# Control.net
KiCad netlist of a schematic drawn in Altium Designer
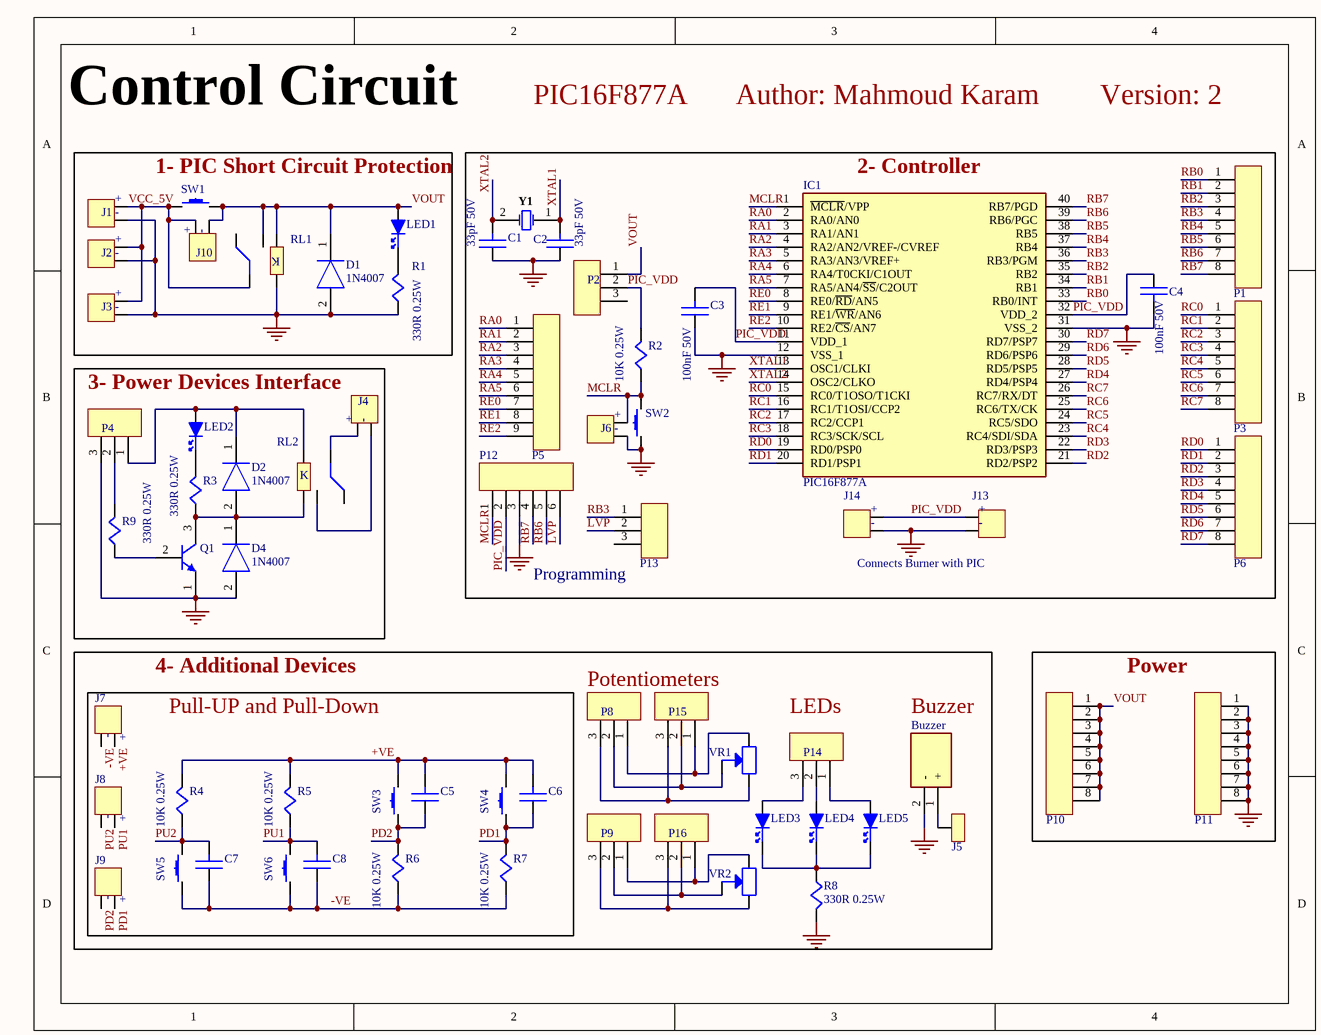
[diagram p0: Control.SchDoc]

(export (version "E")
  (design (tool "Eeschema 10.0.6"))
  (components
    (comp (ref "Buzzer")
      (value "Buzzer 5V")
      (footprint "MyLib:Buzzer 7.62mm pitch 12mm dia")
      (description "Loudspeaker or Buzzer")
      (fields (field (name "MANUFACTURER_PART_NUMBER") "7243178"))
      (libsource (lib "MyLib") (part "Speaker"))
    )
    (comp (ref "C1")
      (value "33pF 50V")
      (footprint "Cap Ceramic 104")
      (description "Capacitor Ceramic")
      (fields
        (field (name "MANUFACTURER") "KEMET")
        (field (name "MANUFACTURER PART NUMBER") "C320C104M5R5TA7301")
      )
      (libsource (lib "MyLib") (part "Ceramic_Capacitors"))
    )
    (comp (ref "C2")
      (value "33pF 50V")
      (footprint "Cap Ceramic 104")
      (description "Capacitor Ceramic")
      (fields
        (field (name "MANUFACTURER") "KEMET")
        (field (name "MANUFACTURER PART NUMBER") "C320C104M5R5TA7301")
      )
      (libsource (lib "MyLib") (part "Ceramic_Capacitors"))
    )
    (comp (ref "C3")
      (value "100nF 50V")
      (footprint "Cap Ceramic 104 2.54")
      (description "Capacitor Ceramic")
      (fields
        (field (name "MANUFACTURER") "KEMET")
        (field (name "MANUFACTURER PART NUMBER") "C320C104M5R5TA7301")
      )
      (libsource (lib "MyLib") (part "Ceramic_Capacitors"))
    )
    (comp (ref "C4")
      (value "100nF 50V")
      (footprint "Cap Ceramic 104 2.54")
      (description "Capacitor Ceramic")
      (fields
        (field (name "MANUFACTURER") "KEMET")
        (field (name "MANUFACTURER PART NUMBER") "C320C104M5R5TA7301")
      )
      (libsource (lib "MyLib") (part "Ceramic_Capacitors"))
    )
    (comp (ref "C5")
      (value "100nF 50V")
      (footprint "Cap Ceramic 104")
      (description "Capacitor Ceramic")
      (fields
        (field (name "MANUFACTURER") "KEMET")
        (field (name "MANUFACTURER PART NUMBER") "C320C104M5R5TA7301")
      )
      (libsource (lib "MyLib") (part "Ceramic_Capacitors"))
    )
    (comp (ref "C6")
      (value "100nF 50V")
      (footprint "Cap Ceramic 104")
      (description "Capacitor Ceramic")
      (fields
        (field (name "MANUFACTURER") "KEMET")
        (field (name "MANUFACTURER PART NUMBER") "C320C104M5R5TA7301")
      )
      (libsource (lib "MyLib") (part "Ceramic_Capacitors"))
    )
    (comp (ref "C7")
      (value "100nF 50V")
      (footprint "Cap Ceramic 104")
      (description "Capacitor Ceramic")
      (fields
        (field (name "MANUFACTURER") "KEMET")
        (field (name "MANUFACTURER PART NUMBER") "C320C104M5R5TA7301")
      )
      (libsource (lib "MyLib") (part "Ceramic_Capacitors"))
    )
    (comp (ref "C8")
      (value "100nF 50V")
      (footprint "Cap Ceramic 104")
      (description "Capacitor Ceramic")
      (fields
        (field (name "MANUFACTURER") "KEMET")
        (field (name "MANUFACTURER PART NUMBER") "C320C104M5R5TA7301")
      )
      (libsource (lib "MyLib") (part "Ceramic_Capacitors"))
    )
    (comp (ref "D1")
      (value "1N4007")
      (footprint "Diode 10.16mm TH H")
      (description "Diodes")
      (fields
        (field (name "MANUFACTURER_PART_NUMBER") "1N4007-E3/53")
        (field (name "MOUSER PART NUMBER") "625-1N4007-E3/53")
      )
      (libsource (lib "MyLib") (part "Diodes"))
    )
    (comp (ref "D2")
      (value "1N4007")
      (footprint "Diode 2.54mm TH V")
      (description "Diodes")
      (fields
        (field (name "MANUFACTURER_PART_NUMBER") "1N4007-E3/53")
        (field (name "MOUSER PART NUMBER") "625-1N4007-E3/53")
      )
      (libsource (lib "MyLib") (part "Diodes"))
    )
    (comp (ref "D4")
      (value "1N4007")
      (footprint "Diode 2.54mm TH V")
      (description "Diodes")
      (fields
        (field (name "MANUFACTURER_PART_NUMBER") "1N4007-E3/53")
        (field (name "MOUSER PART NUMBER") "625-1N4007-E3/53")
      )
      (libsource (lib "MyLib") (part "Diodes"))
    )
    (comp (ref "IC1")
      (value "PIC16F877A")
      (footprint "PIC16F877A TH With Socket")
      (description "Integrated Circuit")
      (fields
        (field (name "MANUFACTURER_PART_NUMBER") "PIC16F877A-I/P")
        (field (name "MOUSER PART NUMBER") "579-PIC16F877A-I/P")
      )
      (libsource (lib "MyLib") (part "PIC16F877A"))
    )
    (comp (ref "J1")
      (value "JST on PCB Connector 2 pins")
      (footprint "JST_B2B TH")
      (description "Terminals 2POS")
      (fields
        (field (name "MANUFACTURER") "Phoenix Contact")
        (field (name "MANUFACTURER PART NUMBER") "1729128")
      )
      (libsource (lib "") (part "Terminal_Block_2Pos_1"))
    )
    (comp (ref "J2")
      (value "Terminal Block Green 5.08mm")
      (footprint "Screw Terminal Block 5.08mm TH Green")
      (description "Terminals 2POS")
      (fields
        (field (name "MANUFACTURER") "Phoenix Contact")
        (field (name "MANUFACTURER PART NUMBER") "1729128")
      )
      (libsource (lib "") (part "Terminal_Block_2Pos_1"))
    )
    (comp (ref "J3")
      (value "DC Power Jack PJ002")
      (footprint "DC Power Jack 2.1mm PJ-002AH TH")
      (description "Terminals 2POS")
      (fields
        (field (name "MANUFACTURER") "Phoenix Contact")
        (field (name "MANUFACTURER PART NUMBER") "1729128")
      )
      (libsource (lib "") (part "Terminal_Block_2Pos_1"))
    )
    (comp (ref "J4")
      (value "Terminal Block Blue 5.08mm")
      (footprint "Screw Terminal Block 5.08mm TH Blue")
      (description "Terminals 2POS")
      (fields
        (field (name "MANUFACTURER") "Phoenix Contact")
        (field (name "MANUFACTURER PART NUMBER") "1729128")
      )
      (libsource (lib "") (part "Terminal_Block_2Pos_2"))
    )
    (comp (ref "J5") (value "Pin") (footprint "Pin") (libsource (lib "MyLib") (part "Pin")))
    (comp (ref "J6")
      (value "Header male 2 ways")
      (footprint "Header Male 2.54mm 2 Pins TH")
      (description "Terminals 2POS")
      (fields
        (field (name "MANUFACTURER") "Phoenix Contact")
        (field (name "MANUFACTURER PART NUMBER") "1729128")
      )
      (libsource (lib "") (part "Terminal_Block_2Pos_1"))
    )
    (comp (ref "J7")
      (value "Header male 2 ways")
      (footprint "Header Male 2.54mm 2 Pins TH")
      (description "Terminals 2POS")
      (fields
        (field (name "MANUFACTURER") "Phoenix Contact")
        (field (name "MANUFACTURER PART NUMBER") "1729128")
      )
      (libsource (lib "MyLib") (part "Terminal_Block_2Pos"))
    )
    (comp (ref "J8")
      (value "Header male 2 ways")
      (footprint "Header Male 2.54mm 2 Pins TH")
      (description "Terminals 2POS")
      (fields
        (field (name "MANUFACTURER") "Phoenix Contact")
        (field (name "MANUFACTURER PART NUMBER") "1729128")
      )
      (libsource (lib "MyLib") (part "Terminal_Block_2Pos"))
    )
    (comp (ref "J9")
      (value "Header male 2 ways")
      (footprint "Header Male 2.54mm 2 Pins TH")
      (description "Terminals 2POS")
      (fields
        (field (name "MANUFACTURER") "Phoenix Contact")
        (field (name "MANUFACTURER PART NUMBER") "1729128")
      )
      (libsource (lib "MyLib") (part "Terminal_Block_2Pos"))
    )
    (comp (ref "J10")
      (value "Header male 2 ways")
      (footprint "Header Male 2.54mm 2 Pins TH")
      (description "Terminals 2POS")
      (fields
        (field (name "MANUFACTURER") "Phoenix Contact")
        (field (name "MANUFACTURER PART NUMBER") "1729128")
      )
      (libsource (lib "") (part "Terminal_Block_2Pos_3"))
    )
    (comp (ref "J13")
      (value "Header male 2 ways")
      (footprint "Header Male 2.54mm 2 Pins TH")
      (description "Terminals 2POS")
      (fields
        (field (name "MANUFACTURER") "Phoenix Contact")
        (field (name "MANUFACTURER PART NUMBER") "1729128")
      )
      (libsource (lib "MyLib") (part "Terminal_Block_2Pos"))
    )
    (comp (ref "J14")
      (value "Header male 2 ways")
      (footprint "Header Male 2.54mm 2 Pins TH")
      (description "Terminals 2POS")
      (fields
        (field (name "MANUFACTURER") "Phoenix Contact")
        (field (name "MANUFACTURER PART NUMBER") "1729128")
      )
      (libsource (lib "") (part "Terminal_Block_2Pos_1"))
    )
    (comp (ref "LED1")
      (value "RED 5mm")
      (footprint "LED 5mm Red TH")
      (description "LEDs")
      (fields
        (field (name "MANUFACTURER") "Vishay Semiconductors")
        (field (name "MANUFACTURER PART NUMBER") "TLDR5400")
      )
      (libsource (lib "MyLib") (part "LEDs_Single"))
    )
    (comp (ref "LED2")
      (value "Green 5mm")
      (footprint "LED 5mm Green TH")
      (description "LEDs")
      (fields
        (field (name "MANUFACTURER") "Vishay Semiconductors")
        (field (name "MANUFACTURER PART NUMBER") "TLDR5400")
      )
      (libsource (lib "MyLib") (part "LEDs_Single"))
    )
    (comp (ref "LED3")
      (value "RED 5mm")
      (footprint "LED 5mm Red TH")
      (description "LEDs")
      (fields
        (field (name "MANUFACTURER") "Vishay Semiconductors")
        (field (name "MANUFACTURER PART NUMBER") "TLDR5400")
      )
      (libsource (lib "MyLib") (part "LEDs_Single"))
    )
    (comp (ref "LED4")
      (value "Green 5mm")
      (footprint "LED 5mm Green TH")
      (description "LEDs")
      (fields
        (field (name "MANUFACTURER") "Vishay Semiconductors")
        (field (name "MANUFACTURER PART NUMBER") "TLDR5400")
      )
      (libsource (lib "MyLib") (part "LEDs_Single"))
    )
    (comp (ref "LED5")
      (value "Yellow 5mm")
      (footprint "LED 5mm Yellow TH")
      (description "LEDs")
      (fields
        (field (name "MANUFACTURER") "Vishay Semiconductors")
        (field (name "MANUFACTURER PART NUMBER") "TLDR5400")
      )
      (libsource (lib "MyLib") (part "LEDs_Single"))
    )
    (comp (ref "P1")
      (value "Header male 8 ways")
      (footprint "Header Male 2.54mm 8 Pins TH")
      (fields (field (name "MANUFACTURER") "3M"))
      (libsource (lib "") (part "Terminal_Block_8Pos_1"))
    )
    (comp (ref "P2")
      (value "Header male 3 ways with jumper")
      (footprint "Header Male 2.54mm 3 Pins with jumper TH")
      (fields (field (name "MANUFACTURER") "3M"))
      (libsource (lib "") (part "Terminal_Block_3Pos_1"))
    )
    (comp (ref "P3")
      (value "Header male 8 ways")
      (footprint "Header Male 2.54mm 8 Pins TH")
      (fields (field (name "MANUFACTURER") "3M"))
      (libsource (lib "") (part "Terminal_Block_8Pos_1"))
    )
    (comp (ref "P4")
      (value "Header male 3 ways")
      (footprint "Header Male 2.54mm 3 Pins TH")
      (fields (field (name "MANUFACTURER") "3M"))
      (libsource (lib "MyLib") (part "Terminal_Block_3Pos"))
    )
    (comp (ref "P5")
      (value "Header male 9 ways")
      (footprint "Header Male 2.54mm 9 Pins TH")
      (fields (field (name "MANUFACTURER") "3M"))
      (libsource (lib "MyLib") (part "Terminal_Block_9Pos"))
    )
    (comp (ref "P6")
      (value "Header male 8 ways")
      (footprint "Header Male 2.54mm 8 Pins TH")
      (fields (field (name "MANUFACTURER") "3M"))
      (libsource (lib "") (part "Terminal_Block_8Pos_1"))
    )
    (comp (ref "P8")
      (value "Header male 3 ways")
      (footprint "Header Male 2.54mm 3 Pins TH")
      (fields (field (name "MANUFACTURER") "3M"))
      (libsource (lib "MyLib") (part "Terminal_Block_3Pos"))
    )
    (comp (ref "P9")
      (value "Header male 3 ways")
      (footprint "Header Male 2.54mm 3 Pins TH")
      (fields (field (name "MANUFACTURER") "3M"))
      (libsource (lib "MyLib") (part "Terminal_Block_3Pos"))
    )
    (comp (ref "P10")
      (value "Header male 8 ways")
      (footprint "Header Male 2.54mm 8 Pins TH")
      (fields (field (name "MANUFACTURER") "3M"))
      (libsource (lib "MyLib") (part "Terminal_Block_8Pos"))
    )
    (comp (ref "P11")
      (value "Header male 8 ways")
      (footprint "Header Male 2.54mm 8 Pins TH")
      (fields (field (name "MANUFACTURER") "3M"))
      (libsource (lib "MyLib") (part "Terminal_Block_8Pos"))
    )
    (comp (ref "P12")
      (value "Header male 6 ways")
      (footprint "Header Male 2.54mm 6 Pins TH")
      (fields (field (name "MANUFACTURER") "3M"))
      (libsource (lib "MyLib") (part "Terminal_Block_6Pos"))
    )
    (comp (ref "P13")
      (value "Header male 3 ways with jumper")
      (footprint "Header Male 2.54mm 3 Pins with jumper TH")
      (fields (field (name "MANUFACTURER") "3M"))
      (libsource (lib "MyLib") (part "Terminal_Block_3Pos"))
    )
    (comp (ref "P14")
      (value "Header male 3 ways")
      (footprint "Header Male 2.54mm 3 Pins TH")
      (fields (field (name "MANUFACTURER") "3M"))
      (libsource (lib "MyLib") (part "Terminal_Block_3Pos"))
    )
    (comp (ref "P15")
      (value "Header male 3 ways")
      (footprint "Header Male 2.54mm 3 Pins TH")
      (fields (field (name "MANUFACTURER") "3M"))
      (libsource (lib "MyLib") (part "Terminal_Block_3Pos"))
    )
    (comp (ref "P16")
      (value "Header male 3 ways")
      (footprint "Header Male 2.54mm 3 Pins TH")
      (fields (field (name "MANUFACTURER") "3M"))
      (libsource (lib "MyLib") (part "Terminal_Block_3Pos"))
    )
    (comp (ref "Q1")
      (value "Transistor PN2222")
      (footprint "PN2222")
      (description "NPN General-Purpose Amplifier, 40 V, -55 to 150 degC, 3-Pin TO-92, RoHS, Bulk")
      (fields (field (name "MANUFACTURER") "Fairchild") (field (name "POWER") "625mW"))
      (libsource (lib "Mahmoud Karam") (part "BJT-NPN-EBC-3"))
    )
    (comp (ref "R1")
      (value "330R 0.25W")
      (footprint "Res 7.62mm H TH")
      (description "Resistors")
      (fields
        (field (name "MANUFACTURER") "Yageo")
        (field (name "MANUFACTURER PART NUMBER") "CFR-25JB-52-100K")
      )
      (libsource (lib "MyLib") (part "Resistors_Single"))
    )
    (comp (ref "R2")
      (value "10K 0.25W")
      (footprint "Res 7.62mm H TH")
      (description "Resistors")
      (fields
        (field (name "MANUFACTURER") "Yageo")
        (field (name "MANUFACTURER PART NUMBER") "CFR-25JB-52-100K")
      )
      (libsource (lib "MyLib") (part "Resistors_Single"))
    )
    (comp (ref "R3")
      (value "330R 0.25W")
      (footprint "Res 2.54mm V TH")
      (description "Resistors")
      (fields
        (field (name "MANUFACTURER") "Yageo")
        (field (name "MANUFACTURER PART NUMBER") "CFR-25JB-52-100K")
      )
      (libsource (lib "MyLib") (part "Resistors_Single"))
    )
    (comp (ref "R4")
      (value "10K 0.25W")
      (footprint "Res 2.54mm V TH")
      (description "Resistors")
      (fields
        (field (name "MANUFACTURER") "Yageo")
        (field (name "MANUFACTURER PART NUMBER") "CFR-25JB-52-100K")
      )
      (libsource (lib "MyLib") (part "Resistors_Single"))
    )
    (comp (ref "R5")
      (value "10K 0.25W")
      (footprint "Res 2.54mm V TH")
      (description "Resistors")
      (fields
        (field (name "MANUFACTURER") "Yageo")
        (field (name "MANUFACTURER PART NUMBER") "CFR-25JB-52-100K")
      )
      (libsource (lib "MyLib") (part "Resistors_Single"))
    )
    (comp (ref "R6")
      (value "10K 0.25W")
      (footprint "Res 2.54mm V TH")
      (description "Resistors")
      (fields
        (field (name "MANUFACTURER") "Yageo")
        (field (name "MANUFACTURER PART NUMBER") "CFR-25JB-52-100K")
      )
      (libsource (lib "MyLib") (part "Resistors_Single"))
    )
    (comp (ref "R7")
      (value "10K 0.25W")
      (footprint "Res 2.54mm V TH")
      (description "Resistors")
      (fields
        (field (name "MANUFACTURER") "Yageo")
        (field (name "MANUFACTURER PART NUMBER") "CFR-25JB-52-100K")
      )
      (libsource (lib "MyLib") (part "Resistors_Single"))
    )
    (comp (ref "R8")
      (value "330R 0.25W")
      (footprint "Res 7.62mm H TH")
      (description "Resistors")
      (fields
        (field (name "MANUFACTURER") "Yageo")
        (field (name "MANUFACTURER PART NUMBER") "CFR-25JB-52-100K")
      )
      (libsource (lib "MyLib") (part "Resistors_Single"))
    )
    (comp (ref "R9")
      (value "330R 0.25W")
      (footprint "Res 2.54mm V TH")
      (description "Resistors")
      (fields
        (field (name "MANUFACTURER") "Yageo")
        (field (name "MANUFACTURER PART NUMBER") "CFR-25JB-52-100K")
      )
      (libsource (lib "MyLib") (part "Resistors_Single"))
    )
    (comp (ref "RL1")
      (value "Relay 5V SRD-05VDC-SL-C")
      (footprint "Relay SRD-05VDC-SL-C")
      (description "Relay SPDT")
      (fields
        (field (name "MANUFACTURER") "TE Connectivity P&B")
        (field (name "MANUFACTURER PART NUMBER") "1-1721150-0")
      )
      (libsource (lib "") (part "Relay_SPDT_1"))
    )
    (comp (ref "RL2")
      (value "Relay 5V SRD-05VDC-SL-C")
      (footprint "Relay SRD-05VDC-SL-C")
      (description "Relay SPDT")
      (fields
        (field (name "MANUFACTURER") "TE Connectivity P&B")
        (field (name "MANUFACTURER PART NUMBER") "1-1721150-0")
      )
      (libsource (lib "MyLib") (part "Relay_SPDT"))
    )
    (comp (ref "SW1")
      (value "Tactile Switch 4 poles")
      (footprint "Tactile switch 6*6*5 TH")
      (description "Switches")
      (fields
        (field (name "MANUFACTURER") "E-Switch")
        (field (name "MANUFACTURER PART NUMBER") "TL1105LF160Q")
      )
      (libsource (lib "MyLib") (part "Switches_2Pos"))
    )
    (comp (ref "SW2")
      (value "Tactile Switch 4 poles")
      (footprint "Tactile switch 6*6*5 TH")
      (description "Switches")
      (fields
        (field (name "MANUFACTURER") "E-Switch")
        (field (name "MANUFACTURER PART NUMBER") "TL1105LF160Q")
      )
      (libsource (lib "") (part "Switches_2Pos_1"))
    )
    (comp (ref "SW3")
      (value "Tactile Switch 4 poles")
      (footprint "Tactile switch 6*6*5 TH")
      (description "Switches")
      (fields
        (field (name "MANUFACTURER") "E-Switch")
        (field (name "MANUFACTURER PART NUMBER") "TL1105LF160Q")
      )
      (libsource (lib "") (part "Switches_2Pos_1"))
    )
    (comp (ref "SW4")
      (value "Tactile Switch 4 poles")
      (footprint "Tactile switch 6*6*5 TH")
      (description "Switches")
      (fields
        (field (name "MANUFACTURER") "E-Switch")
        (field (name "MANUFACTURER PART NUMBER") "TL1105LF160Q")
      )
      (libsource (lib "") (part "Switches_2Pos_1"))
    )
    (comp (ref "SW5")
      (value "Tactile Switch 4 poles")
      (footprint "Tactile switch 6*6*5 TH")
      (description "Switches")
      (fields
        (field (name "MANUFACTURER") "E-Switch")
        (field (name "MANUFACTURER PART NUMBER") "TL1105LF160Q")
      )
      (libsource (lib "") (part "Switches_2Pos_1"))
    )
    (comp (ref "SW6")
      (value "Tactile Switch 4 poles")
      (footprint "Tactile switch 6*6*5 TH")
      (description "Switches")
      (fields
        (field (name "MANUFACTURER") "E-Switch")
        (field (name "MANUFACTURER PART NUMBER") "TL1105LF160Q")
      )
      (libsource (lib "") (part "Switches_2Pos_1"))
    )
    (comp (ref "VR1")
      (value "Potentiometer 10K")
      (footprint "Potentiometer 90 deg dual")
      (description "Variable Resistors")
      (fields
        (field (name "MANUFACTURER") "Bourns")
        (field (name "MANUFACTURER PART NUMBER") "3296W-1-502RLF")
      )
      (libsource (lib "MyLib") (part "VariableResistors"))
    )
    (comp (ref "VR2")
      (value "Potentiometer 10K")
      (footprint "Potentiometer 90 deg dual")
      (description "Variable Resistors")
      (fields
        (field (name "MANUFACTURER") "Bourns")
        (field (name "MANUFACTURER PART NUMBER") "3296W-1-502RLF")
      )
      (libsource (lib "MyLib") (part "VariableResistors"))
    )
    (comp (ref "Y1")
      (value "Crystal 8MHz")
      (footprint "FOX-FOXSLF-2_V")
      (description "Resistance Weld Thru-Hole Crystal, 12 MHz, +/-30 ppm, 20 pF, -20 to 70 degC, 2-Pin THD, RoHS, Bulk")
      (fields (field (name "MANUFACTURER") "FOX Electronics") (field (name "TOLERANCE") "50ppm"))
      (libsource (lib "Mahmoud Karam") (part "XTAL-1-2-2"))
    )
  )
  (nets
    (net (code "1") (name "/+VE") (class "Default")
      (node (ref "C5") (pin "2") (pinfunction "2_2") (pintype "passive"))
      (node (ref "C6") (pin "2") (pinfunction "2_2") (pintype "passive"))
      (node (ref "J7") (pin "1") (pinfunction "1_1") (pintype "passive"))
      (node (ref "R4") (pin "2") (pinfunction "2_2") (pintype "passive"))
      (node (ref "R5") (pin "2") (pinfunction "2_2") (pintype "passive"))
      (node (ref "SW3") (pin "2") (pinfunction "2_2") (pintype "passive"))
      (node (ref "SW4") (pin "2") (pinfunction "2_2") (pintype "passive"))
    )
    (net (code "2") (name "/-VE") (class "Default")
      (node (ref "C7") (pin "1") (pinfunction "1_1") (pintype "passive"))
      (node (ref "C8") (pin "1") (pinfunction "1_1") (pintype "passive"))
      (node (ref "J7") (pin "2") (pinfunction "2_2") (pintype "passive"))
      (node (ref "R6") (pin "1") (pinfunction "1_1") (pintype "passive"))
      (node (ref "R7") (pin "1") (pinfunction "1_1") (pintype "passive"))
      (node (ref "SW5") (pin "1") (pinfunction "1_1") (pintype "passive"))
      (node (ref "SW6") (pin "1") (pinfunction "1_1") (pintype "passive"))
    )
    (net (code "3") (name "/LVP") (class "Default")
      (node (ref "P12") (pin "6") (pinfunction "6_6") (pintype "passive"))
      (node (ref "P13") (pin "2") (pinfunction "2_2") (pintype "passive"))
    )
    (net (code "4") (name "/MCLR") (class "Default")
      (node (ref "IC1") (pin "1") (pinfunction "~{MCLR}/VPP_1") (pintype "passive"))
      (node (ref "J6") (pin "1") (pinfunction "1_1") (pintype "passive"))
      (node (ref "P12") (pin "1") (pinfunction "1_1") (pintype "passive"))
      (node (ref "R2") (pin "1") (pinfunction "1_1") (pintype "passive"))
      (node (ref "SW2") (pin "2") (pinfunction "2_2") (pintype "passive"))
    )
    (net (code "5") (name "/PD1") (class "Default")
      (node (ref "C6") (pin "1") (pinfunction "1_1") (pintype "passive"))
      (node (ref "J9") (pin "1") (pinfunction "1_1") (pintype "passive"))
      (node (ref "R7") (pin "2") (pinfunction "2_2") (pintype "passive"))
      (node (ref "SW4") (pin "1") (pinfunction "1_1") (pintype "passive"))
    )
    (net (code "6") (name "/PD2") (class "Default")
      (node (ref "C5") (pin "1") (pinfunction "1_1") (pintype "passive"))
      (node (ref "J9") (pin "2") (pinfunction "2_2") (pintype "passive"))
      (node (ref "R6") (pin "2") (pinfunction "2_2") (pintype "passive"))
      (node (ref "SW3") (pin "1") (pinfunction "1_1") (pintype "passive"))
    )
    (net (code "7") (name "/PIC_VDD") (class "Default")
      (node (ref "C3") (pin "2") (pinfunction "2_2") (pintype "passive"))
      (node (ref "C4") (pin "1") (pinfunction "1_1") (pintype "passive"))
      (node (ref "IC1") (pin "11") (pinfunction "VDD_1_11") (pintype "passive"))
      (node (ref "IC1") (pin "32") (pinfunction "VDD_2_32") (pintype "passive"))
      (node (ref "J13") (pin "1") (pinfunction "1_1") (pintype "passive"))
      (node (ref "J14") (pin "1") (pinfunction "1_1") (pintype "passive"))
      (node (ref "P12") (pin "2") (pinfunction "2_2") (pintype "passive"))
      (node (ref "P2") (pin "2") (pinfunction "2_2") (pintype "passive"))
      (node (ref "R2") (pin "2") (pinfunction "2_2") (pintype "passive"))
    )
    (net (code "8") (name "/PU1") (class "Default")
      (node (ref "C8") (pin "2") (pinfunction "2_2") (pintype "passive"))
      (node (ref "J8") (pin "1") (pinfunction "1_1") (pintype "passive"))
      (node (ref "R5") (pin "1") (pinfunction "1_1") (pintype "passive"))
      (node (ref "SW6") (pin "2") (pinfunction "2_2") (pintype "passive"))
    )
    (net (code "9") (name "/PU2") (class "Default")
      (node (ref "C7") (pin "2") (pinfunction "2_2") (pintype "passive"))
      (node (ref "J8") (pin "2") (pinfunction "2_2") (pintype "passive"))
      (node (ref "R4") (pin "1") (pinfunction "1_1") (pintype "passive"))
      (node (ref "SW5") (pin "2") (pinfunction "2_2") (pintype "passive"))
    )
    (net (code "10") (name "/RA0") (class "Default")
      (node (ref "IC1") (pin "2") (pinfunction "RA0/AN0_2") (pintype "passive"))
      (node (ref "P5") (pin "1") (pinfunction "1_1") (pintype "passive"))
    )
    (net (code "11") (name "/RA1") (class "Default")
      (node (ref "IC1") (pin "3") (pinfunction "RA1/AN1_3") (pintype "passive"))
      (node (ref "P5") (pin "2") (pinfunction "2_2") (pintype "passive"))
    )
    (net (code "12") (name "/RA2") (class "Default")
      (node (ref "IC1") (pin "4") (pinfunction "RA2/AN2/VREF-/CVREF_4") (pintype "passive"))
      (node (ref "P5") (pin "3") (pinfunction "3_3") (pintype "passive"))
    )
    (net (code "13") (name "/RA3") (class "Default")
      (node (ref "IC1") (pin "5") (pinfunction "RA3/AN3/VREF+_5") (pintype "passive"))
      (node (ref "P5") (pin "4") (pinfunction "4_4") (pintype "passive"))
    )
    (net (code "14") (name "/RA4") (class "Default")
      (node (ref "IC1") (pin "6") (pinfunction "RA4/T0CKI/C1OUT_6") (pintype "passive"))
      (node (ref "P5") (pin "5") (pinfunction "5_5") (pintype "passive"))
    )
    (net (code "15") (name "/RA5") (class "Default")
      (node (ref "IC1") (pin "7") (pinfunction "RA5/AN4/~{SS}/C2OUT_7") (pintype "passive"))
      (node (ref "P5") (pin "6") (pinfunction "6_6") (pintype "passive"))
    )
    (net (code "16") (name "/RB0") (class "Default")
      (node (ref "IC1") (pin "33") (pinfunction "RB0/INT_33") (pintype "passive"))
      (node (ref "P1") (pin "1") (pinfunction "1_1") (pintype "passive"))
    )
    (net (code "17") (name "/RB1") (class "Default")
      (node (ref "IC1") (pin "34") (pinfunction "RB1_34") (pintype "passive"))
      (node (ref "P1") (pin "2") (pinfunction "2_2") (pintype "passive"))
    )
    (net (code "18") (name "/RB2") (class "Default")
      (node (ref "IC1") (pin "35") (pinfunction "RB2_35") (pintype "passive"))
      (node (ref "P1") (pin "3") (pinfunction "3_3") (pintype "passive"))
    )
    (net (code "19") (name "/RB3") (class "Default")
      (node (ref "IC1") (pin "36") (pinfunction "RB3/PGM_36") (pintype "passive"))
      (node (ref "P1") (pin "4") (pinfunction "4_4") (pintype "passive"))
      (node (ref "P13") (pin "1") (pinfunction "1_1") (pintype "passive"))
    )
    (net (code "20") (name "/RB4") (class "Default")
      (node (ref "IC1") (pin "37") (pinfunction "RB4_37") (pintype "passive"))
      (node (ref "P1") (pin "5") (pinfunction "5_5") (pintype "passive"))
    )
    (net (code "21") (name "/RB5") (class "Default")
      (node (ref "IC1") (pin "38") (pinfunction "RB5_38") (pintype "passive"))
      (node (ref "P1") (pin "6") (pinfunction "6_6") (pintype "passive"))
    )
    (net (code "22") (name "/RB6") (class "Default")
      (node (ref "IC1") (pin "39") (pinfunction "RB6/PGC_39") (pintype "passive"))
      (node (ref "P1") (pin "7") (pinfunction "7_7") (pintype "passive"))
      (node (ref "P12") (pin "5") (pinfunction "5_5") (pintype "passive"))
    )
    (net (code "23") (name "/RB7") (class "Default")
      (node (ref "IC1") (pin "40") (pinfunction "RB7/PGD_40") (pintype "passive"))
      (node (ref "P1") (pin "8") (pinfunction "8_8") (pintype "passive"))
      (node (ref "P12") (pin "4") (pinfunction "4_4") (pintype "passive"))
    )
    (net (code "24") (name "/RC0") (class "Default")
      (node (ref "IC1") (pin "15") (pinfunction "RC0/T1OSO/T1CKI_15") (pintype "passive"))
      (node (ref "P3") (pin "1") (pinfunction "1_1") (pintype "passive"))
    )
    (net (code "25") (name "/RC1") (class "Default")
      (node (ref "IC1") (pin "16") (pinfunction "RC1/T1OSI/CCP2_16") (pintype "passive"))
      (node (ref "P3") (pin "2") (pinfunction "2_2") (pintype "passive"))
    )
    (net (code "26") (name "/RC2") (class "Default")
      (node (ref "IC1") (pin "17") (pinfunction "RC2/CCP1_17") (pintype "passive"))
      (node (ref "P3") (pin "3") (pinfunction "3_3") (pintype "passive"))
    )
    (net (code "27") (name "/RC3") (class "Default")
      (node (ref "IC1") (pin "18") (pinfunction "RC3/SCK/SCL_18") (pintype "passive"))
      (node (ref "P3") (pin "4") (pinfunction "4_4") (pintype "passive"))
    )
    (net (code "28") (name "/RC4") (class "Default")
      (node (ref "IC1") (pin "23") (pinfunction "RC4/SDI/SDA_23") (pintype "passive"))
      (node (ref "P3") (pin "5") (pinfunction "5_5") (pintype "passive"))
    )
    (net (code "29") (name "/RC5") (class "Default")
      (node (ref "IC1") (pin "24") (pinfunction "RC5/SDO_24") (pintype "passive"))
      (node (ref "P3") (pin "6") (pinfunction "6_6") (pintype "passive"))
    )
    (net (code "30") (name "/RC6") (class "Default")
      (node (ref "IC1") (pin "25") (pinfunction "RC6/TX/CK_25") (pintype "passive"))
      (node (ref "P3") (pin "7") (pinfunction "7_7") (pintype "passive"))
    )
    (net (code "31") (name "/RC7") (class "Default")
      (node (ref "IC1") (pin "26") (pinfunction "RC7/RX/DT_26") (pintype "passive"))
      (node (ref "P3") (pin "8") (pinfunction "8_8") (pintype "passive"))
    )
    (net (code "32") (name "/RD0") (class "Default")
      (node (ref "IC1") (pin "19") (pinfunction "RD0/PSP0_19") (pintype "passive"))
      (node (ref "P6") (pin "1") (pinfunction "1_1") (pintype "passive"))
    )
    (net (code "33") (name "/RD1") (class "Default")
      (node (ref "IC1") (pin "20") (pinfunction "RD1/PSP1_20") (pintype "passive"))
      (node (ref "P6") (pin "2") (pinfunction "2_2") (pintype "passive"))
    )
    (net (code "34") (name "/RD2") (class "Default")
      (node (ref "IC1") (pin "21") (pinfunction "RD2/PSP2_21") (pintype "passive"))
      (node (ref "P6") (pin "3") (pinfunction "3_3") (pintype "passive"))
    )
    (net (code "35") (name "/RD3") (class "Default")
      (node (ref "IC1") (pin "22") (pinfunction "RD3/PSP3_22") (pintype "passive"))
      (node (ref "P6") (pin "4") (pinfunction "4_4") (pintype "passive"))
    )
    (net (code "36") (name "/RD4") (class "Default")
      (node (ref "IC1") (pin "27") (pinfunction "RD4/PSP4_27") (pintype "passive"))
      (node (ref "P6") (pin "5") (pinfunction "5_5") (pintype "passive"))
    )
    (net (code "37") (name "/RD5") (class "Default")
      (node (ref "IC1") (pin "28") (pinfunction "RD5/PSP5_28") (pintype "passive"))
      (node (ref "P6") (pin "6") (pinfunction "6_6") (pintype "passive"))
    )
    (net (code "38") (name "/RD6") (class "Default")
      (node (ref "IC1") (pin "29") (pinfunction "RD6/PSP6_29") (pintype "passive"))
      (node (ref "P6") (pin "7") (pinfunction "7_7") (pintype "passive"))
    )
    (net (code "39") (name "/RD7") (class "Default")
      (node (ref "IC1") (pin "30") (pinfunction "RD7/PSP7_30") (pintype "passive"))
      (node (ref "P6") (pin "8") (pinfunction "8_8") (pintype "passive"))
    )
    (net (code "40") (name "/RE0") (class "Default")
      (node (ref "IC1") (pin "8") (pinfunction "RE0/~{RD}/AN5_8") (pintype "passive"))
      (node (ref "P5") (pin "7") (pinfunction "7_7") (pintype "passive"))
    )
    (net (code "41") (name "/RE1") (class "Default")
      (node (ref "IC1") (pin "9") (pinfunction "RE1/~{WR}/AN6_9") (pintype "passive"))
      (node (ref "P5") (pin "8") (pinfunction "8_8") (pintype "passive"))
    )
    (net (code "42") (name "/RE2") (class "Default")
      (node (ref "IC1") (pin "10") (pinfunction "RE2/~{CS}/AN7_10") (pintype "passive"))
      (node (ref "P5") (pin "9") (pinfunction "9_9") (pintype "passive"))
    )
    (net (code "43") (name "/VCC_5V") (class "Default")
      (node (ref "J1") (pin "1") (pinfunction "1_1") (pintype "passive"))
      (node (ref "J10") (pin "1") (pinfunction "1_1") (pintype "passive"))
      (node (ref "J2") (pin "1") (pinfunction "1_1") (pintype "passive"))
      (node (ref "J3") (pin "1") (pinfunction "1_1") (pintype "passive"))
      (node (ref "RL1") (pin "1") (pinfunction "COM_1") (pintype "passive"))
      (node (ref "SW1") (pin "1") (pinfunction "1_1") (pintype "passive"))
    )
    (net (code "44") (name "/VOUT") (class "Default")
      (node (ref "D1") (pin "1") (pinfunction "K_1") (pintype "passive"))
      (node (ref "J10") (pin "2") (pinfunction "2_2") (pintype "passive"))
      (node (ref "LED1") (pin "1") (pinfunction "1_1") (pintype "passive"))
      (node (ref "P10") (pin "1") (pinfunction "1_1") (pintype "passive"))
      (node (ref "P10") (pin "2") (pinfunction "2_2") (pintype "passive"))
      (node (ref "P10") (pin "3") (pinfunction "3_3") (pintype "passive"))
      (node (ref "P10") (pin "4") (pinfunction "4_4") (pintype "passive"))
      (node (ref "P10") (pin "5") (pinfunction "5_5") (pintype "passive"))
      (node (ref "P10") (pin "6") (pinfunction "6_6") (pintype "passive"))
      (node (ref "P10") (pin "7") (pinfunction "7_7") (pintype "passive"))
      (node (ref "P10") (pin "8") (pinfunction "8_8") (pintype "passive"))
      (node (ref "P2") (pin "1") (pinfunction "1_1") (pintype "passive"))
      (node (ref "RL1") (pin "3") (pinfunction "3_3") (pintype "passive"))
      (node (ref "RL1") (pin "5") (pinfunction "NO_5") (pintype "passive"))
      (node (ref "SW1") (pin "2") (pinfunction "2_2") (pintype "passive"))
    )
    (net (code "45") (name "/XTAL1") (class "Default")
      (node (ref "C2") (pin "2") (pinfunction "2_2") (pintype "passive"))
      (node (ref "IC1") (pin "13") (pinfunction "OSC1/CLKI_13") (pintype "passive"))
      (node (ref "Y1") (pin "1") (pinfunction "1_1") (pintype "passive"))
    )
    (net (code "46") (name "/XTAL2") (class "Default")
      (node (ref "C1") (pin "2") (pinfunction "2_2") (pintype "passive"))
      (node (ref "IC1") (pin "14") (pinfunction "OSC2/CLKO_14") (pintype "passive"))
      (node (ref "Y1") (pin "2") (pinfunction "2_2") (pintype "passive"))
    )
    (net (code "47") (name "GND") (class "Default")
      (node (ref "Buzzer") (pin "2") (pinfunction "-_2") (pintype "passive"))
      (node (ref "C1") (pin "1") (pinfunction "1_1") (pintype "passive"))
      (node (ref "C2") (pin "1") (pinfunction "1_1") (pintype "passive"))
      (node (ref "C3") (pin "1") (pinfunction "1_1") (pintype "passive"))
      (node (ref "C4") (pin "2") (pinfunction "2_2") (pintype "passive"))
      (node (ref "D1") (pin "2") (pinfunction "A_2") (pintype "passive"))
      (node (ref "D4") (pin "2") (pinfunction "A_2") (pintype "passive"))
      (node (ref "IC1") (pin "12") (pinfunction "VSS_1_12") (pintype "passive"))
      (node (ref "IC1") (pin "31") (pinfunction "VSS_2_31") (pintype "passive"))
      (node (ref "J1") (pin "2") (pinfunction "2_2") (pintype "passive"))
      (node (ref "J13") (pin "2") (pinfunction "2_2") (pintype "passive"))
      (node (ref "J14") (pin "2") (pinfunction "2_2") (pintype "passive"))
      (node (ref "J2") (pin "2") (pinfunction "2_2") (pintype "passive"))
      (node (ref "J3") (pin "2") (pinfunction "2_2") (pintype "passive"))
      (node (ref "J6") (pin "2") (pinfunction "2_2") (pintype "passive"))
      (node (ref "P11") (pin "1") (pinfunction "1_1") (pintype "passive"))
      (node (ref "P11") (pin "2") (pinfunction "2_2") (pintype "passive"))
      (node (ref "P11") (pin "3") (pinfunction "3_3") (pintype "passive"))
      (node (ref "P11") (pin "4") (pinfunction "4_4") (pintype "passive"))
      (node (ref "P11") (pin "5") (pinfunction "5_5") (pintype "passive"))
      (node (ref "P11") (pin "6") (pinfunction "6_6") (pintype "passive"))
      (node (ref "P11") (pin "7") (pinfunction "7_7") (pintype "passive"))
      (node (ref "P11") (pin "8") (pinfunction "8_8") (pintype "passive"))
      (node (ref "P12") (pin "3") (pinfunction "3_3") (pintype "passive"))
      (node (ref "P4") (pin "3") (pinfunction "3_3") (pintype "passive"))
      (node (ref "Q1") (pin "1") (pinfunction "E_1") (pintype "passive"))
      (node (ref "R1") (pin "1") (pinfunction "1_1") (pintype "passive"))
      (node (ref "R8") (pin "2") (pinfunction "2_2") (pintype "passive"))
      (node (ref "RL1") (pin "2") (pinfunction "2_2") (pintype "passive"))
      (node (ref "SW2") (pin "1") (pinfunction "1_1") (pintype "passive"))
    )
    (net (code "48") (name "Net-(Buzzer-+)") (class "Default")
      (node (ref "Buzzer") (pin "1") (pinfunction "+_1") (pintype "passive"))
      (node (ref "J5") (pin "1") (pinfunction "1_1") (pintype "passive"))
    )
    (net (code "49") (name "Net-(D2-A)") (class "Default")
      (node (ref "D2") (pin "2") (pinfunction "A_2") (pintype "passive"))
      (node (ref "D4") (pin "1") (pinfunction "K_1") (pintype "passive"))
      (node (ref "Q1") (pin "3") (pinfunction "C_3") (pintype "passive"))
      (node (ref "R3") (pin "1") (pinfunction "1_1") (pintype "passive"))
      (node (ref "RL2") (pin "3") (pinfunction "3_3") (pintype "passive"))
    )
    (net (code "50") (name "Net-(D2-K)") (class "Default")
      (node (ref "D2") (pin "1") (pinfunction "K_1") (pintype "passive"))
      (node (ref "LED2") (pin "1") (pinfunction "1_1") (pintype "passive"))
      (node (ref "P4") (pin "1") (pinfunction "1_1") (pintype "passive"))
      (node (ref "RL2") (pin "2") (pinfunction "2_2") (pintype "passive"))
    )
    (net (code "51") (name "Net-(LED1-Pad2)") (class "Default")
      (node (ref "LED1") (pin "2") (pinfunction "2_2") (pintype "passive"))
      (node (ref "R1") (pin "2") (pinfunction "2_2") (pintype "passive"))
    )
    (net (code "52") (name "Net-(LED2-Pad2)") (class "Default")
      (node (ref "LED2") (pin "2") (pinfunction "2_2") (pintype "passive"))
      (node (ref "R3") (pin "2") (pinfunction "2_2") (pintype "passive"))
    )
    (net (code "53") (name "Net-(LED3-Pad1)") (class "Default")
      (node (ref "LED3") (pin "1") (pinfunction "1_1") (pintype "passive"))
      (node (ref "P14") (pin "3") (pinfunction "3_3") (pintype "passive"))
    )
    (net (code "54") (name "Net-(LED3-Pad2)") (class "Default")
      (node (ref "LED3") (pin "2") (pinfunction "2_2") (pintype "passive"))
      (node (ref "LED4") (pin "2") (pinfunction "2_2") (pintype "passive"))
      (node (ref "LED5") (pin "2") (pinfunction "2_2") (pintype "passive"))
      (node (ref "R8") (pin "1") (pinfunction "1_1") (pintype "passive"))
    )
    (net (code "55") (name "Net-(LED4-Pad1)") (class "Default")
      (node (ref "LED4") (pin "1") (pinfunction "1_1") (pintype "passive"))
      (node (ref "P14") (pin "2") (pinfunction "2_2") (pintype "passive"))
    )
    (net (code "56") (name "Net-(LED5-Pad1)") (class "Default")
      (node (ref "LED5") (pin "1") (pinfunction "1_1") (pintype "passive"))
      (node (ref "P14") (pin "1") (pinfunction "1_1") (pintype "passive"))
    )
    (net (code "57") (name "Net-(P4-Pad2)") (class "Default")
      (node (ref "P4") (pin "2") (pinfunction "2_2") (pintype "passive"))
      (node (ref "R9") (pin "2") (pinfunction "2_2") (pintype "passive"))
    )
    (net (code "58") (name "Net-(P15-Pad1)") (class "Default")
      (node (ref "P15") (pin "1") (pinfunction "1_1") (pintype "passive"))
      (node (ref "P8") (pin "1") (pinfunction "1_1") (pintype "passive"))
      (node (ref "VR1") (pin "1") (pinfunction "1_1") (pintype "passive"))
    )
    (net (code "59") (name "Net-(P15-Pad2)") (class "Default")
      (node (ref "P15") (pin "2") (pinfunction "2_2") (pintype "passive"))
      (node (ref "P8") (pin "2") (pinfunction "2_2") (pintype "passive"))
      (node (ref "VR1") (pin "2") (pinfunction "2_2") (pintype "passive"))
    )
    (net (code "60") (name "Net-(P15-Pad3)") (class "Default")
      (node (ref "P15") (pin "3") (pinfunction "3_3") (pintype "passive"))
      (node (ref "P8") (pin "3") (pinfunction "3_3") (pintype "passive"))
      (node (ref "VR1") (pin "3") (pinfunction "3_3") (pintype "passive"))
    )
    (net (code "61") (name "Net-(P16-Pad1)") (class "Default")
      (node (ref "P16") (pin "1") (pinfunction "1_1") (pintype "passive"))
      (node (ref "P9") (pin "1") (pinfunction "1_1") (pintype "passive"))
      (node (ref "VR2") (pin "1") (pinfunction "1_1") (pintype "passive"))
    )
    (net (code "62") (name "Net-(P16-Pad2)") (class "Default")
      (node (ref "P16") (pin "2") (pinfunction "2_2") (pintype "passive"))
      (node (ref "P9") (pin "2") (pinfunction "2_2") (pintype "passive"))
      (node (ref "VR2") (pin "2") (pinfunction "2_2") (pintype "passive"))
    )
    (net (code "63") (name "Net-(P16-Pad3)") (class "Default")
      (node (ref "P16") (pin "3") (pinfunction "3_3") (pintype "passive"))
      (node (ref "P9") (pin "3") (pinfunction "3_3") (pintype "passive"))
      (node (ref "VR2") (pin "3") (pinfunction "3_3") (pintype "passive"))
    )
    (net (code "64") (name "Net-(Q1-B)") (class "Default")
      (node (ref "Q1") (pin "2") (pinfunction "B_2") (pintype "passive"))
      (node (ref "R9") (pin "1") (pinfunction "1_1") (pintype "passive"))
    )
    (net (code "65") (name "Net-(RL2-COM)") (class "Default")
      (node (ref "J4") (pin "1") (pinfunction "1_1") (pintype "passive"))
      (node (ref "RL2") (pin "1") (pinfunction "COM_1") (pintype "passive"))
    )
    (net (code "66") (name "Net-(RL2-NO)") (class "Default")
      (node (ref "J4") (pin "2") (pinfunction "2_2") (pintype "passive"))
      (node (ref "RL2") (pin "5") (pinfunction "NO_5") (pintype "passive"))
    )
    (net (code "67") (name "unconnected-(P2-Pad3)") (class "Default")
      (node (ref "P2") (pin "3") (pinfunction "3_3") (pintype "passive"))
    )
    (net (code "68") (name "unconnected-(P13-Pad3)") (class "Default")
      (node (ref "P13") (pin "3") (pinfunction "3_3") (pintype "passive"))
    )
    (net (code "69") (name "unconnected-(RL1-NC-Pad4)") (class "Default")
      (node (ref "RL1") (pin "4") (pinfunction "NC_4") (pintype "passive"))
    )
    (net (code "70") (name "unconnected-(RL2-NC-Pad4)") (class "Default")
      (node (ref "RL2") (pin "4") (pinfunction "NC_4") (pintype "passive"))
    )
  )
)
